# schematic_ult.net
KiCad netlist of a schematic drawn in EAGLE
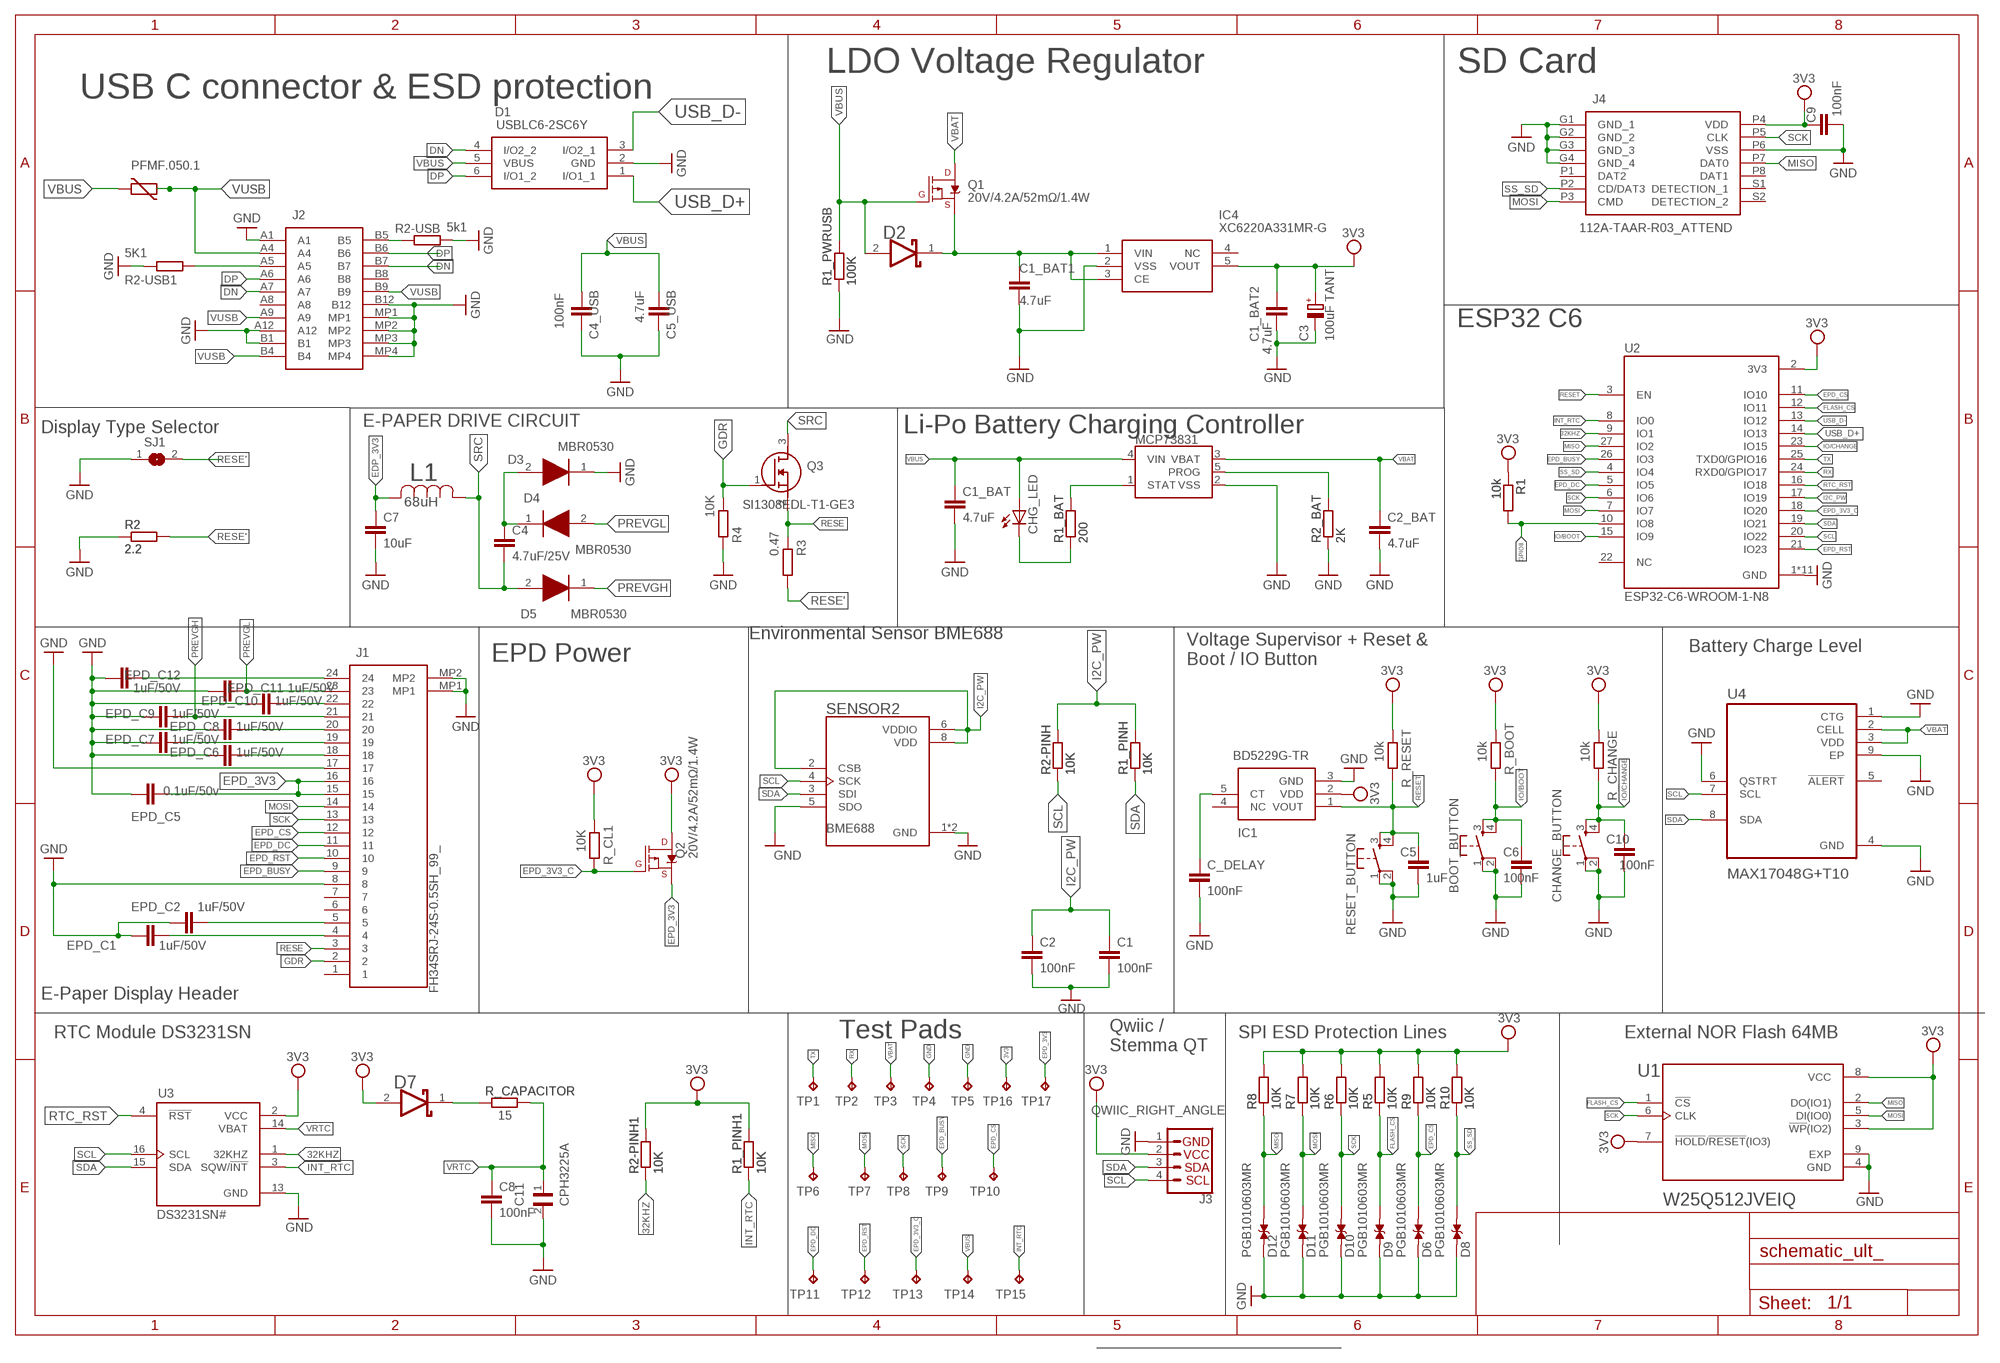
[diagram p0: schematic, sheet 1]

(export (version "E")
  (design (tool "Eeschema 10.0.6"))
  (components
    (comp (ref "BOOT_BUTTON")
      (value "BUTTON_CUSYOMV1")
      (footprint "eagle-import:MYBUTTON")
      (libsource (lib "eagle-import") (part "BUTTON_CUSYOMV1"))
    )
    (comp (ref "C1")
      (value "100nF")
      (footprint "eagle-import:EAGLE-LTSPICE_C0402")
      (libsource (lib "eagle-import") (part "EAGLE-LTSPICE_CC0402"))
    )
    (comp (ref "C1_BAT")
      (value "4.7uF")
      (footprint "eagle-import:EAGLE-LTSPICE_C0402")
      (libsource (lib "eagle-import") (part "EAGLE-LTSPICE_CC0402"))
    )
    (comp (ref "C1_BAT1")
      (value "4.7uF")
      (footprint "eagle-import:ESP32_WROVER_EAGLE-LTSPICE_C0402")
      (libsource (lib "eagle-import") (part "ESP32_WROVER_EAGLE-LTSPICE_CC0402"))
    )
    (comp (ref "C1_BAT2")
      (value "4.7uF")
      (footprint "eagle-import:ESP32_WROVER_EAGLE-LTSPICE_C0402")
      (libsource (lib "eagle-import") (part "ESP32_WROVER_EAGLE-LTSPICE_CC0402"))
    )
    (comp (ref "C2")
      (value "100nF")
      (footprint "eagle-import:EAGLE-LTSPICE_C0402")
      (libsource (lib "eagle-import") (part "EAGLE-LTSPICE_CC0402"))
    )
    (comp (ref "C2_BAT")
      (value "4.7uF")
      (footprint "eagle-import:EAGLE-LTSPICE_C0402")
      (libsource (lib "eagle-import") (part "EAGLE-LTSPICE_CC0402"))
    )
    (comp (ref "C3")
      (value "100uF TANT")
      (footprint "eagle-import:RCL_CT3528")
      (libsource (lib "eagle-import") (part "RCL_CPOL-EUCT3528"))
    )
    (comp (ref "C4")
      (value "4.7uF/25V")
      (footprint "eagle-import:EAGLE-LTSPICE_C0402")
      (libsource (lib "eagle-import") (part "EAGLE-LTSPICE_CC0402"))
    )
    (comp (ref "C4_USB")
      (value "100nF")
      (footprint "eagle-import:EAGLE-LTSPICE_C0402")
      (libsource (lib "eagle-import") (part "EAGLE-LTSPICE_CC0402"))
    )
    (comp (ref "C5")
      (value "1uF")
      (footprint "eagle-import:EAGLE-LTSPICE_C0402")
      (libsource (lib "eagle-import") (part "EAGLE-LTSPICE_CC0402"))
    )
    (comp (ref "C5_USB")
      (value "4.7uF")
      (footprint "eagle-import:EAGLE-LTSPICE_C0402")
      (libsource (lib "eagle-import") (part "EAGLE-LTSPICE_CC0402"))
    )
    (comp (ref "C6")
      (value "100nF")
      (footprint "eagle-import:EAGLE-LTSPICE_C0402")
      (libsource (lib "eagle-import") (part "EAGLE-LTSPICE_CC0402"))
    )
    (comp (ref "C7")
      (value "10uF")
      (footprint "eagle-import:EAGLE-LTSPICE_C0402")
      (libsource (lib "eagle-import") (part "EAGLE-LTSPICE_CC0402"))
    )
    (comp (ref "C8")
      (value "100nF")
      (footprint "eagle-import:EAGLE-LTSPICE_C0402")
      (libsource (lib "eagle-import") (part "EAGLE-LTSPICE_CC0402"))
    )
    (comp (ref "C9")
      (value "100nF")
      (footprint "eagle-import:EAGLE-LTSPICE_C0402")
      (libsource (lib "eagle-import") (part "EAGLE-LTSPICE_CC0402"))
    )
    (comp (ref "C10")
      (value "100nF")
      (footprint "eagle-import:EAGLE-LTSPICE_C0402")
      (libsource (lib "eagle-import") (part "EAGLE-LTSPICE_CC0402"))
    )
    (comp (ref "C11")
      (value "CPH3225A")
      (footprint "eagle-import:CAPCP3225X100N")
      (fields (field (name "MF") "Seiko Instruments"))
      (libsource (lib "eagle-import") (part "CPH3225A"))
    )
    (comp (ref "CHANGE_BUTTON")
      (value "BUTTON_CUSYOMV1")
      (footprint "eagle-import:MYBUTTON")
      (libsource (lib "eagle-import") (part "BUTTON_CUSYOMV1"))
    )
    (comp (ref "CHG_LED")
      (value "ADAFRUIT_LEDCHIP-LED0603")
      (footprint "eagle-import:ADAFRUIT_CHIP-LED0603")
      (libsource (lib "eagle-import") (part "ADAFRUIT_LEDCHIP-LED0603"))
    )
    (comp (ref "C_DELAY")
      (value "100nF")
      (footprint "eagle-import:EAGLE-LTSPICE_C0402")
      (libsource (lib "eagle-import") (part "EAGLE-LTSPICE_CC0402"))
    )
    (comp (ref "D1")
      (value "USBLC6-2SC6Y")
      (footprint "eagle-import:SOT95P280X145-6N")
      (fields (field (name "MF") "STMicroelectronics"))
      (libsource (lib "eagle-import") (part "USBLC6-2SC6Y"))
    )
    (comp (ref "D2")
      (value "ESP32_WROVER_AVX---SD0805S020S1R0_AVX_SD0805S020S1R0_0_0AVX_SD0805S020S1R0_0_0")
      (footprint "eagle-import:ESP32_WROVER_AVX---SD0805S020S1R0_AVX_SD0805S020S1R0_0")
      (fields
        (field (name "DIGIKEY_PART_NUMBER") "478-7800-1-ND")
        (field (name "MF") "AVX")
        (field (name "MOUSER_PART_NUMBER") "581-SD0805S020S1R0")
      )
      (libsource (lib "eagle-import") (part "ESP32_WROVER_AVX---SD0805S020S1R0_AVX_SD0805S020S1R0_0_0AVX_SD0805S020S1R0_0_0"))
    )
    (comp (ref "D3")
      (value "MBR0530")
      (footprint "eagle-import:SOD3716X135N")
      (fields (field (name "MF") "ON Semiconductor"))
      (libsource (lib "eagle-import") (part "MBR0530"))
    )
    (comp (ref "D4")
      (value "MBR0530")
      (footprint "eagle-import:SOD3716X135N")
      (fields (field (name "MF") "ON Semiconductor"))
      (libsource (lib "eagle-import") (part "MBR0530"))
    )
    (comp (ref "D5")
      (value "MBR0530")
      (footprint "eagle-import:SOD3716X135N")
      (fields (field (name "MF") "ON Semiconductor"))
      (libsource (lib "eagle-import") (part "MBR0530"))
    )
    (comp (ref "D6")
      (value "PGB1010603MR")
      (footprint "eagle-import:DIOC1608X36N")
      (fields (field (name "MF") "Littelfuse Inc."))
      (libsource (lib "eagle-import") (part "PGB1010603MR"))
    )
    (comp (ref "D7")
      (value "ESP32_WROVER_AVX---SD0805S020S1R0_AVX_SD0805S020S1R0_0_0AVX_SD0805S020S1R0_0_0")
      (footprint "eagle-import:ESP32_WROVER_AVX---SD0805S020S1R0_AVX_SD0805S020S1R0_0")
      (fields
        (field (name "DIGIKEY_PART_NUMBER") "478-7800-1-ND")
        (field (name "MF") "AVX")
        (field (name "MOUSER_PART_NUMBER") "581-SD0805S020S1R0")
      )
      (libsource (lib "eagle-import") (part "ESP32_WROVER_AVX---SD0805S020S1R0_AVX_SD0805S020S1R0_0_0AVX_SD0805S020S1R0_0_0"))
    )
    (comp (ref "D8")
      (value "PGB1010603MR")
      (footprint "eagle-import:DIOC1608X36N")
      (fields (field (name "MF") "Littelfuse Inc."))
      (libsource (lib "eagle-import") (part "PGB1010603MR"))
    )
    (comp (ref "D9")
      (value "PGB1010603MR")
      (footprint "eagle-import:DIOC1608X36N")
      (fields (field (name "MF") "Littelfuse Inc."))
      (libsource (lib "eagle-import") (part "PGB1010603MR"))
    )
    (comp (ref "D10")
      (value "PGB1010603MR")
      (footprint "eagle-import:DIOC1608X36N")
      (fields (field (name "MF") "Littelfuse Inc."))
      (libsource (lib "eagle-import") (part "PGB1010603MR"))
    )
    (comp (ref "D11")
      (value "PGB1010603MR")
      (footprint "eagle-import:DIOC1608X36N")
      (fields (field (name "MF") "Littelfuse Inc."))
      (libsource (lib "eagle-import") (part "PGB1010603MR"))
    )
    (comp (ref "D12")
      (value "PGB1010603MR")
      (footprint "eagle-import:DIOC1608X36N")
      (fields (field (name "MF") "Littelfuse Inc."))
      (libsource (lib "eagle-import") (part "PGB1010603MR"))
    )
    (comp (ref "EPD_C1")
      (value "1uF/50V")
      (footprint "eagle-import:EAGLE-LTSPICE_C0402")
      (libsource (lib "eagle-import") (part "EAGLE-LTSPICE_CC0402"))
    )
    (comp (ref "EPD_C2")
      (value "1uF/50V")
      (footprint "eagle-import:EAGLE-LTSPICE_C0402")
      (libsource (lib "eagle-import") (part "EAGLE-LTSPICE_CC0402"))
    )
    (comp (ref "EPD_C5")
      (value "0.1uF/50v")
      (footprint "eagle-import:EAGLE-LTSPICE_C0402")
      (libsource (lib "eagle-import") (part "EAGLE-LTSPICE_CC0402"))
    )
    (comp (ref "EPD_C6")
      (value "1uF/50V")
      (footprint "eagle-import:EAGLE-LTSPICE_C0402")
      (libsource (lib "eagle-import") (part "EAGLE-LTSPICE_CC0402"))
    )
    (comp (ref "EPD_C7")
      (value "1uF/50V")
      (footprint "eagle-import:EAGLE-LTSPICE_C0402")
      (libsource (lib "eagle-import") (part "EAGLE-LTSPICE_CC0402"))
    )
    (comp (ref "EPD_C8")
      (value "1uF/50V")
      (footprint "eagle-import:EAGLE-LTSPICE_C0402")
      (libsource (lib "eagle-import") (part "EAGLE-LTSPICE_CC0402"))
    )
    (comp (ref "EPD_C9")
      (value "1uF/50V")
      (footprint "eagle-import:EAGLE-LTSPICE_C0402")
      (libsource (lib "eagle-import") (part "EAGLE-LTSPICE_CC0402"))
    )
    (comp (ref "EPD_C10")
      (value "1uF/50V")
      (footprint "eagle-import:EAGLE-LTSPICE_C0402")
      (libsource (lib "eagle-import") (part "EAGLE-LTSPICE_CC0402"))
    )
    (comp (ref "EPD_C11")
      (value "1uF/50V")
      (footprint "eagle-import:EAGLE-LTSPICE_C0402")
      (libsource (lib "eagle-import") (part "EAGLE-LTSPICE_CC0402"))
    )
    (comp (ref "EPD_C12")
      (value "1uF/50V")
      (footprint "eagle-import:EAGLE-LTSPICE_C0402")
      (libsource (lib "eagle-import") (part "EAGLE-LTSPICE_CC0402"))
    )
    (comp (ref "IC1")
      (value "BD5229G-TR")
      (footprint "eagle-import:SOT95P280X125-5N")
      (fields (field (name "MOUSER_PART_NUMBER") "755-BD5229G-TR"))
      (libsource (lib "eagle-import") (part "BD5229G-TR"))
    )
    (comp (ref "IC4")
      (value "XC6220A331MR-G")
      (footprint "eagle-import:SOT95P280X120-5N")
      (fields (field (name "MOUSER_PART_NUMBER") "865-XC6220A331MR-G"))
      (libsource (lib "eagle-import") (part "XC6220A331MR-G"))
    )
    (comp (ref "J1")
      (value "FH34SRJ-24S-0.5SH_99_")
      (footprint "eagle-import:FH34SRJ24S05SH99")
      (fields
        (field (name "MANUFACTURER_PART_NUMBER") "FH34SRJ-24S-0.5SH(99)")
        (field (name "MOUSER_PART_NUMBER") "798-FH34SRJ24S05SH99")
      )
      (libsource (lib "eagle-import") (part "FH34SRJ-24S-0.5SH_99_"))
    )
    (comp (ref "J2")
      (value "SAMACSYS_PARTS_USB4110-GF-A")
      (footprint "eagle-import:SAMACSYS_PARTS_USB4110GFA")
      (fields
        (field (name "MANUFACTURER_PART_NUMBER") "USB4110-GF-A")
        (field (name "MOUSER_PART_NUMBER") "640-USB4110-GF-A")
      )
      (libsource (lib "eagle-import") (part "SAMACSYS_PARTS_USB4110-GF-A"))
    )
    (comp (ref "J3")
      (value "QWIIC_RIGHT_ANGLE")
      (footprint "eagle-import:JST04_1MM_RA")
      (libsource (lib "eagle-import") (part "QWIIC_CONNECTORJS-1MM"))
    )
    (comp (ref "J4")
      (value "112A-TAAR-R03_ATTEND")
      (footprint "eagle-import:112ATAARR03ATTEND")
      (fields (field (name "MANUFACTURER_PART_NUMBER") "112A-TAAR-R03 ATTEND"))
      (libsource (lib "eagle-import") (part "112A-TAAR-R03_ATTEND"))
    )
    (comp (ref "L1")
      (value "68uH")
      (footprint "eagle-import:IND_4828-WE-TPC_WRE")
      (fields
        (field (name "MANUFACTURER_PART_NUMBER") "744043680")
        (field (name "COPYRIGHT") "Copyright (C) 2024 Ultra Librarian. All rights reserved.")
      )
      (libsource (lib "eagle-import") (part "744043680IND_4828-WE-TPC_WRE"))
    )
    (comp (ref "MCP73831")
      (value "ESP32_WROVER_SPARKFUN-IC-POWER_MCP73831")
      (footprint "eagle-import:ESP32_WROVER_SPARKFUN-IC-POWER_SOT23-5")
      (libsource (lib "eagle-import") (part "ESP32_WROVER_SPARKFUN-IC-POWER_MCP73831"))
    )
    (comp (ref "PFMF.050.1")
      (value "ESP32C6_VARISTORCN1812")
      (footprint "eagle-import:ESP32C6_VARISTOR_CT_CN1812")
      (libsource (lib "eagle-import") (part "ESP32C6_VARISTORCN1812"))
    )
    (comp (ref "Q1")
      (value "20V/4.2A/52mΩ/1.4W")
      (footprint "eagle-import:ESP32_WROVER_SPARKFUN-DISCRETESEMI_SOT23-3")
      (libsource (lib "eagle-import") (part "ESP32_WROVER_SPARKFUN-DISCRETESEMI_MOSFET_PCH-DMG2305UX-7"))
    )
    (comp (ref "Q2")
      (value "20V/4.2A/52mΩ/1.4W")
      (footprint "eagle-import:ESP32_WROVER_SPARKFUN-DISCRETESEMI_SOT23-3")
      (libsource (lib "eagle-import") (part "ESP32_WROVER_SPARKFUN-DISCRETESEMI_MOSFET_PCH-DMG2305UX-7"))
    )
    (comp (ref "Q3")
      (value "SI1308EDL-T1-GE3")
      (footprint "eagle-import:SOT65P210X110-3N")
      (fields (field (name "MF") "Vishay Siliconix"))
      (libsource (lib "eagle-import") (part "SI1308EDL-T1-GE3"))
    )
    (comp (ref "R1")
      (value "10k")
      (footprint "eagle-import:ESP32_WROVER_EAGLE-LTSPICE_R0402")
      (libsource (lib "eagle-import") (part "ESP32_WROVER_EAGLE-LTSPICE_RR0402"))
    )
    (comp (ref "R1_BAT")
      (value "200")
      (footprint "eagle-import:ESP32_WROVER_EAGLE-LTSPICE_R0402")
      (libsource (lib "eagle-import") (part "ESP32_WROVER_EAGLE-LTSPICE_RR0402"))
    )
    (comp (ref "R1_PINH")
      (value "10K")
      (footprint "eagle-import:ESP32_WROVER_EAGLE-LTSPICE_R0402")
      (libsource (lib "eagle-import") (part "ESP32_WROVER_EAGLE-LTSPICE_RR0402"))
    )
    (comp (ref "R1_PINH1")
      (value "10K")
      (footprint "eagle-import:ESP32_WROVER_EAGLE-LTSPICE_R0402")
      (libsource (lib "eagle-import") (part "ESP32_WROVER_EAGLE-LTSPICE_RR0402"))
    )
    (comp (ref "R1_PWRUSB")
      (value "100K")
      (footprint "eagle-import:ESP32_WROVER_EAGLE-LTSPICE_R0402")
      (libsource (lib "eagle-import") (part "ESP32_WROVER_EAGLE-LTSPICE_RR0402"))
    )
    (comp (ref "R2")
      (value "2.2")
      (footprint "eagle-import:ESP32_WROVER_EAGLE-LTSPICE_R0402")
      (libsource (lib "eagle-import") (part "ESP32_WROVER_EAGLE-LTSPICE_RR0402"))
    )
    (comp (ref "R2-PINH")
      (value "10K")
      (footprint "eagle-import:ESP32_WROVER_EAGLE-LTSPICE_R0402")
      (libsource (lib "eagle-import") (part "ESP32_WROVER_EAGLE-LTSPICE_RR0402"))
    )
    (comp (ref "R2-PINH1")
      (value "10K")
      (footprint "eagle-import:ESP32_WROVER_EAGLE-LTSPICE_R0402")
      (libsource (lib "eagle-import") (part "ESP32_WROVER_EAGLE-LTSPICE_RR0402"))
    )
    (comp (ref "R2-USB")
      (value "5k1")
      (footprint "eagle-import:ESP32_WROVER_EAGLE-LTSPICE_R0402")
      (libsource (lib "eagle-import") (part "ESP32_WROVER_EAGLE-LTSPICE_RR0402"))
    )
    (comp (ref "R2-USB1")
      (value "5K1")
      (footprint "eagle-import:ESP32_WROVER_EAGLE-LTSPICE_R0402")
      (fields (field (name "SPICEPREFIX") "R2-USB1"))
      (libsource (lib "eagle-import") (part "ESP32_WROVER_EAGLE-LTSPICE_RR0402"))
    )
    (comp (ref "R2_BAT")
      (value "2K")
      (footprint "eagle-import:ESP32_WROVER_EAGLE-LTSPICE_R0402")
      (libsource (lib "eagle-import") (part "ESP32_WROVER_EAGLE-LTSPICE_RR0402"))
    )
    (comp (ref "R3")
      (value "0.47")
      (footprint "eagle-import:ESP32_WROVER_EAGLE-LTSPICE_R0402")
      (libsource (lib "eagle-import") (part "ESP32_WROVER_EAGLE-LTSPICE_RR0402"))
    )
    (comp (ref "R4")
      (value "10K")
      (footprint "eagle-import:ESP32_WROVER_EAGLE-LTSPICE_R0402")
      (libsource (lib "eagle-import") (part "ESP32_WROVER_EAGLE-LTSPICE_RR0402"))
    )
    (comp (ref "R5")
      (value "10K")
      (footprint "eagle-import:ESP32_WROVER_EAGLE-LTSPICE_R0402")
      (libsource (lib "eagle-import") (part "ESP32_WROVER_EAGLE-LTSPICE_RR0402"))
    )
    (comp (ref "R6")
      (value "10K")
      (footprint "eagle-import:ESP32_WROVER_EAGLE-LTSPICE_R0402")
      (libsource (lib "eagle-import") (part "ESP32_WROVER_EAGLE-LTSPICE_RR0402"))
    )
    (comp (ref "R7")
      (value "10K")
      (footprint "eagle-import:ESP32_WROVER_EAGLE-LTSPICE_R0402")
      (libsource (lib "eagle-import") (part "ESP32_WROVER_EAGLE-LTSPICE_RR0402"))
    )
    (comp (ref "R8")
      (value "10K")
      (footprint "eagle-import:ESP32_WROVER_EAGLE-LTSPICE_R0402")
      (libsource (lib "eagle-import") (part "ESP32_WROVER_EAGLE-LTSPICE_RR0402"))
    )
    (comp (ref "R9")
      (value "10K")
      (footprint "eagle-import:ESP32_WROVER_EAGLE-LTSPICE_R0402")
      (libsource (lib "eagle-import") (part "ESP32_WROVER_EAGLE-LTSPICE_RR0402"))
    )
    (comp (ref "R10")
      (value "10K")
      (footprint "eagle-import:ESP32_WROVER_EAGLE-LTSPICE_R0402")
      (libsource (lib "eagle-import") (part "ESP32_WROVER_EAGLE-LTSPICE_RR0402"))
    )
    (comp (ref "RESET_BUTTON")
      (value "BUTTON_CUSYOMV1")
      (footprint "eagle-import:MYBUTTON")
      (libsource (lib "eagle-import") (part "BUTTON_CUSYOMV1"))
    )
    (comp (ref "R_BOOT")
      (value "10k")
      (footprint "eagle-import:ESP32_WROVER_EAGLE-LTSPICE_R0402")
      (libsource (lib "eagle-import") (part "ESP32_WROVER_EAGLE-LTSPICE_RR0402"))
    )
    (comp (ref "R_CAPACITOR")
      (value "15")
      (footprint "eagle-import:ESP32_WROVER_EAGLE-LTSPICE_R0402")
      (libsource (lib "eagle-import") (part "ESP32_WROVER_EAGLE-LTSPICE_RR0402"))
    )
    (comp (ref "R_CHANGE")
      (value "10k")
      (footprint "eagle-import:ESP32_WROVER_EAGLE-LTSPICE_R0402")
      (libsource (lib "eagle-import") (part "ESP32_WROVER_EAGLE-LTSPICE_RR0402"))
    )
    (comp (ref "R_CL1")
      (value "10K")
      (footprint "eagle-import:ESP32_WROVER_EAGLE-LTSPICE_R0402")
      (libsource (lib "eagle-import") (part "ESP32_WROVER_EAGLE-LTSPICE_RR0402"))
    )
    (comp (ref "R_RESET")
      (value "10k")
      (footprint "eagle-import:ESP32_WROVER_EAGLE-LTSPICE_R0402")
      (libsource (lib "eagle-import") (part "ESP32_WROVER_EAGLE-LTSPICE_RR0402"))
    )
    (comp (ref "SENSOR2")
      (value "ESP32_WROVER_BME680_BME680")
      (footprint "eagle-import:ESP32_WROVER_BME680_PSON80P300X300X100-8N")
      (fields (field (name "MF") "Bosch Sensortec") (field (name "MP") "BME680"))
      (libsource (lib "eagle-import") (part "ESP32_WROVER_BME680_BME680"))
    )
    (comp (ref "SJ1") (value "SJ") (footprint "eagle-import:SJ") (libsource (lib "eagle-import") (part "SJ")))
    (comp (ref "TP1")
      (value "TPTP20R")
      (footprint "eagle-import:TP20R")
      (libsource (lib "eagle-import") (part "TPTP20R"))
    )
    (comp (ref "TP2")
      (value "TPTP20R")
      (footprint "eagle-import:TP20R")
      (libsource (lib "eagle-import") (part "TPTP20R"))
    )
    (comp (ref "TP3")
      (value "TPTP20R")
      (footprint "eagle-import:TP20R")
      (libsource (lib "eagle-import") (part "TPTP20R"))
    )
    (comp (ref "TP4")
      (value "TPTP20R")
      (footprint "eagle-import:TP20R")
      (libsource (lib "eagle-import") (part "TPTP20R"))
    )
    (comp (ref "TP5")
      (value "TPTP20R")
      (footprint "eagle-import:TP20R")
      (libsource (lib "eagle-import") (part "TPTP20R"))
    )
    (comp (ref "TP6")
      (value "TPTP20R")
      (footprint "eagle-import:TP20R")
      (libsource (lib "eagle-import") (part "TPTP20R"))
    )
    (comp (ref "TP7")
      (value "TPTP20R")
      (footprint "eagle-import:TP20R")
      (libsource (lib "eagle-import") (part "TPTP20R"))
    )
    (comp (ref "TP8")
      (value "TPTP20R")
      (footprint "eagle-import:TP20R")
      (libsource (lib "eagle-import") (part "TPTP20R"))
    )
    (comp (ref "TP9")
      (value "TPTP20R")
      (footprint "eagle-import:TP20R")
      (libsource (lib "eagle-import") (part "TPTP20R"))
    )
    (comp (ref "TP10")
      (value "TPTP20R")
      (footprint "eagle-import:TP20R")
      (libsource (lib "eagle-import") (part "TPTP20R"))
    )
    (comp (ref "TP11")
      (value "TPTP20R")
      (footprint "eagle-import:TP20R")
      (libsource (lib "eagle-import") (part "TPTP20R"))
    )
    (comp (ref "TP12")
      (value "TPTP20R")
      (footprint "eagle-import:TP20R")
      (libsource (lib "eagle-import") (part "TPTP20R"))
    )
    (comp (ref "TP13")
      (value "TPTP20R")
      (footprint "eagle-import:TP20R")
      (libsource (lib "eagle-import") (part "TPTP20R"))
    )
    (comp (ref "TP14")
      (value "TPTP20R")
      (footprint "eagle-import:TP20R")
      (libsource (lib "eagle-import") (part "TPTP20R"))
    )
    (comp (ref "TP15")
      (value "TPTP20R")
      (footprint "eagle-import:TP20R")
      (libsource (lib "eagle-import") (part "TPTP20R"))
    )
    (comp (ref "TP16")
      (value "TPTP20R")
      (footprint "eagle-import:TP20R")
      (libsource (lib "eagle-import") (part "TPTP20R"))
    )
    (comp (ref "TP17")
      (value "TPTP20R")
      (footprint "eagle-import:TP20R")
      (libsource (lib "eagle-import") (part "TPTP20R"))
    )
    (comp (ref "U1")
      (value "W25Q512JVEIQ")
      (footprint "eagle-import:SON127P600X800X80-9N")
      (fields (field (name "MF") "Winbond Electronics"))
      (libsource (lib "eagle-import") (part "W25Q512JVEIQ"))
    )
    (comp (ref "U2")
      (value "ESP32-C6-WROOM-1-N8")
      (footprint "eagle-import:XCVR_ESP32-C6-WROOM-1-N8")
      (fields (field (name "MF") "Espressif Systems"))
      (libsource (lib "eagle-import") (part "ESP32-C6-WROOM-1-N8"))
    )
    (comp (ref "U3")
      (value "DS3231SN#")
      (footprint "eagle-import:SOIC127P1032X265-16N")
      (fields (field (name "MF") "Analog Devices"))
      (libsource (lib "eagle-import") (part "DS3231SN#"))
    )
    (comp (ref "U4")
      (value "MAX17048G+T10")
      (footprint "eagle-import:SON50P200X200X80-9N")
      (fields (field (name "MF") "Analog Devices"))
      (libsource (lib "eagle-import") (part "MAX17048G+T10"))
    )
  )
  (nets
    (net (code "1") (name "3V3") (class "Default")
      (node (ref "C1_BAT2") (pin "1") (pinfunction "1_1") (pintype "passive"))
      (node (ref "C3") (pin "+") (pinfunction "+_+") (pintype "passive"))
      (node (ref "C9") (pin "2") (pinfunction "2_2") (pintype "passive"))
      (node (ref "D7") (pin "2") (pinfunction "ANODE_2") (pintype "bidirectional"))
      (node (ref "IC1") (pin "2") (pinfunction "VDD_2") (pintype "bidirectional"))
      (node (ref "IC4") (pin "5") (pinfunction "VOUT_5") (pintype "bidirectional"))
      (node (ref "J3") (pin "2") (pinfunction "2_2") (pintype "power_in"))
      (node (ref "J4") (pin "P4") (pinfunction "VDD_P4") (pintype "bidirectional"))
      (node (ref "Q2") (pin "3") (pinfunction "D_3") (pintype "bidirectional"))
      (node (ref "R1") (pin "1") (pinfunction "1_1") (pintype "passive"))
      (node (ref "R10") (pin "2") (pinfunction "2_2") (pintype "passive"))
      (node (ref "R1_PINH1") (pin "2") (pinfunction "2_2") (pintype "passive"))
      (node (ref "R2-PINH1") (pin "2") (pinfunction "2_2") (pintype "passive"))
      (node (ref "R5") (pin "2") (pinfunction "2_2") (pintype "passive"))
      (node (ref "R6") (pin "2") (pinfunction "2_2") (pintype "passive"))
      (node (ref "R7") (pin "2") (pinfunction "2_2") (pintype "passive"))
      (node (ref "R8") (pin "2") (pinfunction "2_2") (pintype "passive"))
      (node (ref "R9") (pin "2") (pinfunction "2_2") (pintype "passive"))
      (node (ref "R_BOOT") (pin "2") (pinfunction "2_2") (pintype "passive"))
      (node (ref "R_CHANGE") (pin "2") (pinfunction "2_2") (pintype "passive"))
      (node (ref "R_CL1") (pin "2") (pinfunction "2_2") (pintype "passive"))
      (node (ref "R_RESET") (pin "2") (pinfunction "2_2") (pintype "passive"))
      (node (ref "TP16") (pin "TP") (pinfunction "TP_TP") (pintype "input"))
      (node (ref "U1") (pin "3") (pinfunction "~{WP}(IO2)_3") (pintype "bidirectional"))
      (node (ref "U1") (pin "7") (pinfunction "~{HOLD}/~{RESET}(IO3)_7") (pintype "bidirectional"))
      (node (ref "U1") (pin "8") (pinfunction "VCC_8") (pintype "power_in"))
      (node (ref "U2") (pin "2") (pinfunction "3V3_2") (pintype "power_in"))
      (node (ref "U3") (pin "2") (pinfunction "VCC_2") (pintype "power_in"))
    )
    (net (code "2") (name "32KHZ") (class "Default")
      (node (ref "R2-PINH1") (pin "1") (pinfunction "1_1") (pintype "passive"))
      (node (ref "U2") (pin "9") (pinfunction "IO1_9") (pintype "bidirectional"))
      (node (ref "U3") (pin "1") (pinfunction "32KHZ_1") (pintype "output"))
    )
    (net (code "3") (name "DN") (class "Default")
      (node (ref "D1") (pin "4") (pinfunction "I/O2_2_4") (pintype "bidirectional"))
      (node (ref "J2") (pin "A7") (pinfunction "A7_A7") (pintype "bidirectional"))
      (node (ref "J2") (pin "B7") (pinfunction "B7_B7") (pintype "bidirectional"))
    )
    (net (code "4") (name "DP") (class "Default")
      (node (ref "D1") (pin "6") (pinfunction "I/O1_2_6") (pintype "bidirectional"))
      (node (ref "J2") (pin "A6") (pinfunction "A6_A6") (pintype "bidirectional"))
      (node (ref "J2") (pin "B6") (pinfunction "B6_B6") (pintype "bidirectional"))
    )
    (net (code "5") (name "EDP_3V3") (class "Default")
      (node (ref "C7") (pin "1") (pinfunction "1_1") (pintype "passive"))
      (node (ref "L1") (pin "2") (pinfunction "2_2") (pintype "passive"))
    )
    (net (code "6") (name "EPD_3V3") (class "Default")
      (node (ref "EPD_C5") (pin "2") (pinfunction "2_2") (pintype "passive"))
      (node (ref "J1") (pin "15") (pinfunction "15_15") (pintype "bidirectional"))
      (node (ref "J1") (pin "16") (pinfunction "16_16") (pintype "bidirectional"))
      (node (ref "Q2") (pin "2") (pinfunction "S_2") (pintype "bidirectional"))
      (node (ref "TP17") (pin "TP") (pinfunction "TP_TP") (pintype "input"))
    )
    (net (code "7") (name "EPD_3V3_C") (class "Default")
      (node (ref "Q2") (pin "1") (pinfunction "G_1") (pintype "bidirectional"))
      (node (ref "R_CL1") (pin "1") (pinfunction "1_1") (pintype "passive"))
      (node (ref "TP13") (pin "TP") (pinfunction "TP_TP") (pintype "input"))
      (node (ref "U2") (pin "18") (pinfunction "IO20_18") (pintype "bidirectional"))
    )
    (net (code "8") (name "EPD_BUSY") (class "Default")
      (node (ref "J1") (pin "9") (pinfunction "9_9") (pintype "bidirectional"))
      (node (ref "TP9") (pin "TP") (pinfunction "TP_TP") (pintype "input"))
      (node (ref "U2") (pin "26") (pinfunction "IO3_26") (pintype "bidirectional"))
    )
    (net (code "9") (name "EPD_CS") (class "Default")
      (node (ref "D6") (pin "2") (pinfunction "2_2") (pintype "passive"))
      (node (ref "J1") (pin "12") (pinfunction "12_12") (pintype "bidirectional"))
      (node (ref "R9") (pin "1") (pinfunction "1_1") (pintype "passive"))
      (node (ref "TP10") (pin "TP") (pinfunction "TP_TP") (pintype "input"))
      (node (ref "U2") (pin "11") (pinfunction "IO10_11") (pintype "bidirectional"))
    )
    (net (code "10") (name "EPD_DC") (class "Default")
      (node (ref "J1") (pin "11") (pinfunction "11_11") (pintype "bidirectional"))
      (node (ref "TP11") (pin "TP") (pinfunction "TP_TP") (pintype "input"))
      (node (ref "U2") (pin "5") (pinfunction "IO5_5") (pintype "bidirectional"))
    )
    (net (code "11") (name "EPD_RST") (class "Default")
      (node (ref "J1") (pin "10") (pinfunction "10_10") (pintype "bidirectional"))
      (node (ref "TP12") (pin "TP") (pinfunction "TP_TP") (pintype "input"))
      (node (ref "U2") (pin "21") (pinfunction "IO23_21") (pintype "bidirectional"))
    )
    (net (code "12") (name "FLASH_CS") (class "Default")
      (node (ref "D9") (pin "2") (pinfunction "2_2") (pintype "passive"))
      (node (ref "R5") (pin "1") (pinfunction "1_1") (pintype "passive"))
      (node (ref "U1") (pin "1") (pinfunction "~{CS}_1") (pintype "input"))
      (node (ref "U2") (pin "12") (pinfunction "IO11_12") (pintype "bidirectional"))
    )
    (net (code "13") (name "GDR") (class "Default")
      (node (ref "J1") (pin "2") (pinfunction "2_2") (pintype "bidirectional"))
      (node (ref "Q3") (pin "1") (pinfunction "G_1") (pintype "bidirectional"))
      (node (ref "R4") (pin "2") (pinfunction "2_2") (pintype "passive"))
    )
    (net (code "14") (name "GND") (class "Default")
      (node (ref "BOOT_BUTTON") (pin "1") (pinfunction "1_1") (pintype "passive"))
      (node (ref "BOOT_BUTTON") (pin "2") (pinfunction "2_2") (pintype "passive"))
      (node (ref "C1") (pin "2") (pinfunction "2_2") (pintype "passive"))
      (node (ref "C10") (pin "2") (pinfunction "2_2") (pintype "passive"))
      (node (ref "C11") (pin "2") (pinfunction "2_2") (pintype "passive"))
      (node (ref "C1_BAT") (pin "2") (pinfunction "2_2") (pintype "passive"))
      (node (ref "C1_BAT1") (pin "2") (pinfunction "2_2") (pintype "passive"))
      (node (ref "C1_BAT2") (pin "2") (pinfunction "2_2") (pintype "passive"))
      (node (ref "C2") (pin "2") (pinfunction "2_2") (pintype "passive"))
      (node (ref "C2_BAT") (pin "2") (pinfunction "2_2") (pintype "passive"))
      (node (ref "C3") (pin "-") (pinfunction "-_-") (pintype "passive"))
      (node (ref "C4_USB") (pin "2") (pinfunction "2_2") (pintype "passive"))
      (node (ref "C5") (pin "2") (pinfunction "2_2") (pintype "passive"))
      (node (ref "C5_USB") (pin "2") (pinfunction "2_2") (pintype "passive"))
      (node (ref "C6") (pin "2") (pinfunction "2_2") (pintype "passive"))
      (node (ref "C7") (pin "2") (pinfunction "2_2") (pintype "passive"))
      (node (ref "C8") (pin "2") (pinfunction "2_2") (pintype "passive"))
      (node (ref "C9") (pin "1") (pinfunction "1_1") (pintype "passive"))
      (node (ref "CHANGE_BUTTON") (pin "1") (pinfunction "1_1") (pintype "passive"))
      (node (ref "CHANGE_BUTTON") (pin "2") (pinfunction "2_2") (pintype "passive"))
      (node (ref "C_DELAY") (pin "2") (pinfunction "2_2") (pintype "passive"))
      (node (ref "D1") (pin "2") (pinfunction "GND_2") (pintype "bidirectional"))
      (node (ref "D10") (pin "1") (pinfunction "1_1") (pintype "passive"))
      (node (ref "D11") (pin "1") (pinfunction "1_1") (pintype "passive"))
      (node (ref "D12") (pin "1") (pinfunction "1_1") (pintype "passive"))
      (node (ref "D3") (pin "1") (pinfunction "K_1") (pintype "bidirectional"))
      (node (ref "D6") (pin "1") (pinfunction "1_1") (pintype "passive"))
      (node (ref "D8") (pin "1") (pinfunction "1_1") (pintype "passive"))
      (node (ref "D9") (pin "1") (pinfunction "1_1") (pintype "passive"))
      (node (ref "EPD_C1") (pin "1") (pinfunction "1_1") (pintype "passive"))
      (node (ref "EPD_C10") (pin "1") (pinfunction "1_1") (pintype "passive"))
      (node (ref "EPD_C11") (pin "1") (pinfunction "1_1") (pintype "passive"))
      (node (ref "EPD_C12") (pin "1") (pinfunction "1_1") (pintype "passive"))
      (node (ref "EPD_C2") (pin "1") (pinfunction "1_1") (pintype "passive"))
      (node (ref "EPD_C5") (pin "1") (pinfunction "1_1") (pintype "passive"))
      (node (ref "EPD_C6") (pin "1") (pinfunction "1_1") (pintype "passive"))
      (node (ref "EPD_C7") (pin "1") (pinfunction "1_1") (pintype "passive"))
      (node (ref "EPD_C8") (pin "1") (pinfunction "1_1") (pintype "passive"))
      (node (ref "EPD_C9") (pin "1") (pinfunction "1_1") (pintype "passive"))
      (node (ref "IC1") (pin "3") (pinfunction "GND_3") (pintype "bidirectional"))
      (node (ref "IC4") (pin "2") (pinfunction "VSS_2") (pintype "bidirectional"))
      (node (ref "J1") (pin "17") (pinfunction "17_17") (pintype "bidirectional"))
      (node (ref "J1") (pin "8") (pinfunction "8_8") (pintype "bidirectional"))
      (node (ref "J1") (pin "MP1") (pinfunction "MP1_MP1") (pintype "bidirectional"))
      (node (ref "J1") (pin "MP2") (pinfunction "MP2_MP2") (pintype "bidirectional"))
      (node (ref "J2") (pin "A1") (pinfunction "A1_A1") (pintype "bidirectional"))
      (node (ref "J2") (pin "A12") (pinfunction "A12_A12") (pintype "bidirectional"))
      (node (ref "J2") (pin "B1") (pinfunction "B1_B1") (pintype "bidirectional"))
      (node (ref "J2") (pin "B12") (pinfunction "B12_B12") (pintype "bidirectional"))
      (node (ref "J2") (pin "MP1") (pinfunction "MP1_MP1") (pintype "bidirectional"))
      (node (ref "J2") (pin "MP2") (pinfunction "MP2_MP2") (pintype "bidirectional"))
      (node (ref "J2") (pin "MP3") (pinfunction "MP3_MP3") (pintype "bidirectional"))
      (node (ref "J2") (pin "MP4") (pinfunction "MP4_MP4") (pintype "bidirectional"))
      (node (ref "J3") (pin "1") (pinfunction "1_1") (pintype "power_in"))
      (node (ref "J4") (pin "G1") (pinfunction "GND_1_G1") (pintype "bidirectional"))
      (node (ref "J4") (pin "G2") (pinfunction "GND_2_G2") (pintype "bidirectional"))
      (node (ref "J4") (pin "G3") (pinfunction "GND_3_G3") (pintype "bidirectional"))
      (node (ref "J4") (pin "G4") (pinfunction "GND_4_G4") (pintype "bidirectional"))
      (node (ref "J4") (pin "P6") (pinfunction "VSS_P6") (pintype "bidirectional"))
      (node (ref "MCP73831") (pin "2") (pinfunction "VSS_2") (pintype "power_in"))
      (node (ref "R1_PWRUSB") (pin "1") (pinfunction "1_1") (pintype "passive"))
      (node (ref "R2") (pin "1") (pinfunction "1_1") (pintype "passive"))
      (node (ref "R2-USB") (pin "2") (pinfunction "2_2") (pintype "passive"))
      (node (ref "R2-USB1") (pin "1") (pinfunction "1_1") (pintype "passive"))
      (node (ref "R2_BAT") (pin "1") (pinfunction "1_1") (pintype "passive"))
      (node (ref "R4") (pin "1") (pinfunction "1_1") (pintype "passive"))
      (node (ref "RESET_BUTTON") (pin "1") (pinfunction "1_1") (pintype "passive"))
      (node (ref "RESET_BUTTON") (pin "2") (pinfunction "2_2") (pintype "passive"))
      (node (ref "SENSOR2") (pin "1") (pinfunction "GND_1") (pintype "power_in"))
      (node (ref "SENSOR2") (pin "5") (pinfunction "SDO_5") (pintype "bidirectional"))
      (node (ref "SENSOR2") (pin "7") (pinfunction "GND_7") (pintype "power_in"))
      (node (ref "SJ1") (pin "1") (pinfunction "1_1") (pintype "passive"))
      (node (ref "TP4") (pin "TP") (pinfunction "TP_TP") (pintype "input"))
      (node (ref "TP5") (pin "TP") (pinfunction "TP_TP") (pintype "input"))
      (node (ref "U1") (pin "4") (pinfunction "GND_4") (pintype "power_in"))
      (node (ref "U1") (pin "9") (pinfunction "EXP_9") (pintype "passive"))
      (node (ref "U2") (pin "1") (pinfunction "GND_1") (pintype "power_in"))
      (node (ref "U2") (pin "28") (pinfunction "GND_28") (pintype "power_in"))
      (node (ref "U2") (pin "29_1") (pinfunction "GND_29_1") (pintype "power_in"))
      (node (ref "U2") (pin "29_2") (pinfunction "GND_29_2") (pintype "power_in"))
      (node (ref "U2") (pin "29_3") (pinfunction "GND_29_3") (pintype "power_in"))
      (node (ref "U2") (pin "29_4") (pinfunction "GND_29_4") (pintype "power_in"))
      (node (ref "U2") (pin "29_5") (pinfunction "GND_29_5") (pintype "power_in"))
      (node (ref "U2") (pin "29_6") (pinfunction "GND_29_6") (pintype "power_in"))
      (node (ref "U2") (pin "29_7") (pinfunction "GND_29_7") (pintype "power_in"))
      (node (ref "U2") (pin "29_8") (pinfunction "GND_29_8") (pintype "power_in"))
      (node (ref "U2") (pin "29_9") (pinfunction "GND_29_9") (pintype "power_in"))
      (node (ref "U3") (pin "13") (pinfunction "GND_13") (pintype "power_in"))
      (node (ref "U4") (pin "1") (pinfunction "CTG_1") (pintype "power_in"))
      (node (ref "U4") (pin "4") (pinfunction "GND_4") (pintype "power_in"))
      (node (ref "U4") (pin "6") (pinfunction "QSTRT_6") (pintype "input"))
      (node (ref "U4") (pin "9") (pinfunction "EP_9") (pintype "power_in"))
    )
    (net (code "15") (name "GPIO8") (class "Default")
      (node (ref "R1") (pin "2") (pinfunction "2_2") (pintype "passive"))
      (node (ref "U2") (pin "10") (pinfunction "IO8_10") (pintype "bidirectional"))
    )
    (net (code "16") (name "I2C_PW") (class "Default")
      (node (ref "C1") (pin "1") (pinfunction "1_1") (pintype "passive"))
      (node (ref "C2") (pin "1") (pinfunction "1_1") (pintype "passive"))
      (node (ref "R1_PINH") (pin "2") (pinfunction "2_2") (pintype "passive"))
      (node (ref "R2-PINH") (pin "2") (pinfunction "2_2") (pintype "passive"))
      (node (ref "SENSOR2") (pin "2") (pinfunction "CSB_2") (pintype "input"))
      (node (ref "SENSOR2") (pin "6") (pinfunction "VDDIO_6") (pintype "power_in"))
      (node (ref "SENSOR2") (pin "8") (pinfunction "VDD_8") (pintype "power_in"))
      (node (ref "U2") (pin "17") (pinfunction "IO19_17") (pintype "bidirectional"))
    )
    (net (code "17") (name "INT_RTC") (class "Default")
      (node (ref "R1_PINH1") (pin "1") (pinfunction "1_1") (pintype "passive"))
      (node (ref "TP15") (pin "TP") (pinfunction "TP_TP") (pintype "input"))
      (node (ref "U2") (pin "8") (pinfunction "IO0_8") (pintype "bidirectional"))
      (node (ref "U3") (pin "3") (pinfunction "SQW/~{INT}_3") (pintype "output"))
    )
    (net (code "18") (name "IO{slash}BOOT") (class "Default")
      (node (ref "BOOT_BUTTON") (pin "3") (pinfunction "3_3") (pintype "passive"))
      (node (ref "BOOT_BUTTON") (pin "4") (pinfunction "4_4") (pintype "passive"))
      (node (ref "C6") (pin "1") (pinfunction "1_1") (pintype "passive"))
      (node (ref "R_BOOT") (pin "1") (pinfunction "1_1") (pintype "passive"))
      (node (ref "U2") (pin "15") (pinfunction "IO9_15") (pintype "bidirectional"))
    )
    (net (code "19") (name "IO{slash}CHANGE") (class "Default")
      (node (ref "C10") (pin "1") (pinfunction "1_1") (pintype "passive"))
      (node (ref "CHANGE_BUTTON") (pin "3") (pinfunction "3_3") (pintype "passive"))
      (node (ref "CHANGE_BUTTON") (pin "4") (pinfunction "4_4") (pintype "passive"))
      (node (ref "R_CHANGE") (pin "1") (pinfunction "1_1") (pintype "passive"))
      (node (ref "U2") (pin "23") (pinfunction "IO15_23") (pintype "bidirectional"))
    )
    (net (code "20") (name "MISO") (class "Default")
      (node (ref "D12") (pin "2") (pinfunction "2_2") (pintype "passive"))
      (node (ref "J4") (pin "P7") (pinfunction "DAT0_P7") (pintype "bidirectional"))
      (node (ref "R8") (pin "1") (pinfunction "1_1") (pintype "passive"))
      (node (ref "TP6") (pin "TP") (pinfunction "TP_TP") (pintype "input"))
      (node (ref "U1") (pin "2") (pinfunction "DO(IO1)_2") (pintype "bidirectional"))
      (node (ref "U2") (pin "27") (pinfunction "IO2_27") (pintype "bidirectional"))
    )
    (net (code "21") (name "MOSI") (class "Default")
      (node (ref "D11") (pin "2") (pinfunction "2_2") (pintype "passive"))
      (node (ref "J1") (pin "14") (pinfunction "14_14") (pintype "bidirectional"))
      (node (ref "J4") (pin "P3") (pinfunction "CMD_P3") (pintype "bidirectional"))
      (node (ref "R7") (pin "1") (pinfunction "1_1") (pintype "passive"))
      (node (ref "TP7") (pin "TP") (pinfunction "TP_TP") (pintype "input"))
      (node (ref "U1") (pin "5") (pinfunction "DI(IO0)_5") (pintype "bidirectional"))
      (node (ref "U2") (pin "7") (pinfunction "IO7_7") (pintype "bidirectional"))
    )
    (net (code "22") (name "Net-(CHG_LED-PadC)") (class "Default")
      (node (ref "CHG_LED") (pin "C") (pinfunction "C_C") (pintype "passive"))
      (node (ref "R1_BAT") (pin "1") (pinfunction "1_1") (pintype "passive"))
    )
    (net (code "23") (name "Net-(D2-CATHODE)") (class "Default")
      (node (ref "C1_BAT1") (pin "1") (pinfunction "1_1") (pintype "passive"))
      (node (ref "D2") (pin "1") (pinfunction "CATHODE_1") (pintype "bidirectional"))
      (node (ref "IC4") (pin "1") (pinfunction "VIN_1") (pintype "bidirectional"))
      (node (ref "IC4") (pin "3") (pinfunction "CE_3") (pintype "bidirectional"))
      (node (ref "Q1") (pin "2") (pinfunction "S_2") (pintype "bidirectional"))
    )
    (net (code "24") (name "Net-(D3-A)") (class "Default")
      (node (ref "C4") (pin "1") (pinfunction "1_1") (pintype "passive"))
      (node (ref "D3") (pin "2") (pinfunction "A_2") (pintype "bidirectional"))
      (node (ref "D4") (pin "1") (pinfunction "K_1") (pintype "bidirectional"))
    )
    (net (code "25") (name "Net-(D7-CATHODE)") (class "Default")
      (node (ref "D7") (pin "1") (pinfunction "CATHODE_1") (pintype "bidirectional"))
      (node (ref "R_CAPACITOR") (pin "1") (pinfunction "1_1") (pintype "passive"))
    )
    (net (code "26") (name "Net-(EPD_C1-Pad2)") (class "Default")
      (node (ref "EPD_C1") (pin "2") (pinfunction "2_2") (pintype "passive"))
      (node (ref "J1") (pin "4") (pinfunction "4_4") (pintype "bidirectional"))
    )
    (net (code "27") (name "Net-(EPD_C2-Pad2)") (class "Default")
      (node (ref "EPD_C2") (pin "2") (pinfunction "2_2") (pintype "passive"))
      (node (ref "J1") (pin "5") (pinfunction "5_5") (pintype "bidirectional"))
    )
    (net (code "28") (name "Net-(EPD_C6-Pad2)") (class "Default")
      (node (ref "EPD_C6") (pin "2") (pinfunction "2_2") (pintype "passive"))
      (node (ref "J1") (pin "18") (pinfunction "18_18") (pintype "bidirectional"))
    )
    (net (code "29") (name "Net-(EPD_C7-Pad2)") (class "Default")
      (node (ref "EPD_C7") (pin "2") (pinfunction "2_2") (pintype "passive"))
      (node (ref "J1") (pin "19") (pinfunction "19_19") (pintype "bidirectional"))
    )
    (net (code "30") (name "Net-(EPD_C8-Pad2)") (class "Default")
      (node (ref "EPD_C8") (pin "2") (pinfunction "2_2") (pintype "passive"))
      (node (ref "J1") (pin "20") (pinfunction "20_20") (pintype "bidirectional"))
    )
    (net (code "31") (name "Net-(EPD_C10-Pad2)") (class "Default")
      (node (ref "EPD_C10") (pin "2") (pinfunction "2_2") (pintype "passive"))
      (node (ref "J1") (pin "22") (pinfunction "22_22") (pintype "bidirectional"))
    )
    (net (code "32") (name "Net-(EPD_C12-Pad2)") (class "Default")
      (node (ref "EPD_C12") (pin "2") (pinfunction "2_2") (pintype "passive"))
      (node (ref "J1") (pin "24") (pinfunction "24_24") (pintype "bidirectional"))
    )
    (net (code "33") (name "Net-(IC1-CT)") (class "Default")
      (node (ref "C_DELAY") (pin "1") (pinfunction "1_1") (pintype "passive"))
      (node (ref "IC1") (pin "5") (pinfunction "CT_5") (pintype "bidirectional"))
    )
    (net (code "34") (name "Net-(J2-PadA5)") (class "Default")
      (node (ref "J2") (pin "A5") (pinfunction "A5_A5") (pintype "bidirectional"))
      (node (ref "R2-USB1") (pin "2") (pinfunction "2_2") (pintype "passive"))
    )
    (net (code "35") (name "Net-(J2-PadB5)") (class "Default")
      (node (ref "J2") (pin "B5") (pinfunction "B5_B5") (pintype "bidirectional"))
      (node (ref "R2-USB") (pin "1") (pinfunction "1_1") (pintype "passive"))
    )
    (net (code "36") (name "Net-(MCP73831-PROG)") (class "Default")
      (node (ref "MCP73831") (pin "5") (pinfunction "PROG_5") (pintype "input"))
      (node (ref "R2_BAT") (pin "2") (pinfunction "2_2") (pintype "passive"))
    )
    (net (code "37") (name "Net-(MCP73831-STAT)") (class "Default")
      (node (ref "MCP73831") (pin "1") (pinfunction "STAT_1") (pintype "output"))
      (node (ref "R1_BAT") (pin "2") (pinfunction "2_2") (pintype "passive"))
    )
    (net (code "38") (name "PREVGH") (class "Default")
      (node (ref "D5") (pin "1") (pinfunction "K_1") (pintype "bidirectional"))
      (node (ref "EPD_C9") (pin "2") (pinfunction "2_2") (pintype "passive"))
      (node (ref "J1") (pin "21") (pinfunction "21_21") (pintype "bidirectional"))
    )
    (net (code "39") (name "PREVGL") (class "Default")
      (node (ref "D4") (pin "2") (pinfunction "A_2") (pintype "bidirectional"))
      (node (ref "EPD_C11") (pin "2") (pinfunction "2_2") (pintype "passive"))
      (node (ref "J1") (pin "23") (pinfunction "23_23") (pintype "bidirectional"))
    )
    (net (code "40") (name "RESE") (class "Default")
      (node (ref "J1") (pin "3") (pinfunction "3_3") (pintype "bidirectional"))
      (node (ref "Q3") (pin "2") (pinfunction "S_2") (pintype "bidirectional"))
      (node (ref "R3") (pin "2") (pinfunction "2_2") (pintype "passive"))
    )
    (net (code "41") (name "RESE'") (class "Default")
      (node (ref "R2") (pin "2") (pinfunction "2_2") (pintype "passive"))
      (node (ref "R3") (pin "1") (pinfunction "1_1") (pintype "passive"))
      (node (ref "SJ1") (pin "2") (pinfunction "2_2") (pintype "passive"))
    )
    (net (code "42") (name "RESET") (class "Default")
      (node (ref "C5") (pin "1") (pinfunction "1_1") (pintype "passive"))
      (node (ref "IC1") (pin "1") (pinfunction "VOUT_1") (pintype "bidirectional"))
      (node (ref "RESET_BUTTON") (pin "3") (pinfunction "3_3") (pintype "passive"))
      (node (ref "RESET_BUTTON") (pin "4") (pinfunction "4_4") (pintype "passive"))
      (node (ref "R_RESET") (pin "1") (pinfunction "1_1") (pintype "passive"))
      (node (ref "U2") (pin "3") (pinfunction "EN_3") (pintype "input"))
    )
    (net (code "43") (name "RTC_RST") (class "Default")
      (node (ref "U2") (pin "16") (pinfunction "IO18_16") (pintype "bidirectional"))
      (node (ref "U3") (pin "4") (pinfunction "~{RST}_4") (pintype "input"))
    )
    (net (code "44") (name "RX") (class "Default")
      (node (ref "TP2") (pin "TP") (pinfunction "TP_TP") (pintype "input"))
      (node (ref "U2") (pin "24") (pinfunction "RXD0/GPIO17_24") (pintype "bidirectional"))
    )
    (net (code "45") (name "SCK") (class "Default")
      (node (ref "D10") (pin "2") (pinfunction "2_2") (pintype "passive"))
      (node (ref "J1") (pin "13") (pinfunction "13_13") (pintype "bidirectional"))
      (node (ref "J4") (pin "P5") (pinfunction "CLK_P5") (pintype "bidirectional"))
      (node (ref "R6") (pin "1") (pinfunction "1_1") (pintype "passive"))
      (node (ref "TP8") (pin "TP") (pinfunction "TP_TP") (pintype "input"))
      (node (ref "U1") (pin "6") (pinfunction "CLK_6") (pintype "input"))
      (node (ref "U2") (pin "6") (pinfunction "IO6_6") (pintype "bidirectional"))
    )
    (net (code "46") (name "SCL") (class "Default")
      (node (ref "J3") (pin "4") (pinfunction "4_4") (pintype "passive"))
      (node (ref "R2-PINH") (pin "1") (pinfunction "1_1") (pintype "passive"))
      (node (ref "SENSOR2") (pin "4") (pinfunction "SCK_4") (pintype "input"))
      (node (ref "U2") (pin "20") (pinfunction "IO22_20") (pintype "bidirectional"))
      (node (ref "U3") (pin "16") (pinfunction "SCL_16") (pintype "input"))
      (node (ref "U4") (pin "7") (pinfunction "SCL_7") (pintype "input"))
    )
    (net (code "47") (name "SDA") (class "Default")
      (node (ref "J3") (pin "3") (pinfunction "3_3") (pintype "passive"))
      (node (ref "R1_PINH") (pin "1") (pinfunction "1_1") (pintype "passive"))
      (node (ref "SENSOR2") (pin "3") (pinfunction "SDI_3") (pintype "bidirectional"))
      (node (ref "U2") (pin "19") (pinfunction "IO21_19") (pintype "bidirectional"))
      (node (ref "U3") (pin "15") (pinfunction "SDA_15") (pintype "bidirectional"))
      (node (ref "U4") (pin "8") (pinfunction "SDA_8") (pintype "bidirectional"))
    )
    (net (code "48") (name "SRC") (class "Default")
      (node (ref "C4") (pin "2") (pinfunction "2_2") (pintype "passive"))
      (node (ref "D5") (pin "2") (pinfunction "A_2") (pintype "bidirectional"))
      (node (ref "L1") (pin "1") (pinfunction "1_1") (pintype "passive"))
      (node (ref "Q3") (pin "3") (pinfunction "D_3") (pintype "bidirectional"))
    )
    (net (code "49") (name "SS_SD") (class "Default")
      (node (ref "D8") (pin "2") (pinfunction "2_2") (pintype "passive"))
      (node (ref "J4") (pin "P2") (pinfunction "CD/DAT3_P2") (pintype "bidirectional"))
      (node (ref "R10") (pin "1") (pinfunction "1_1") (pintype "passive"))
      (node (ref "U2") (pin "4") (pinfunction "IO4_4") (pintype "bidirectional"))
    )
    (net (code "50") (name "TX") (class "Default")
      (node (ref "TP1") (pin "TP") (pinfunction "TP_TP") (pintype "input"))
      (node (ref "U2") (pin "25") (pinfunction "TXD0/GPIO16_25") (pintype "bidirectional"))
    )
    (net (code "51") (name "USB_D+") (class "Default")
      (node (ref "D1") (pin "1") (pinfunction "I/O1_1_1") (pintype "bidirectional"))
      (node (ref "U2") (pin "14") (pinfunction "IO13_14") (pintype "bidirectional"))
    )
    (net (code "52") (name "USB_D-") (class "Default")
      (node (ref "D1") (pin "3") (pinfunction "I/O2_1_3") (pintype "bidirectional"))
      (node (ref "U2") (pin "13") (pinfunction "IO12_13") (pintype "bidirectional"))
    )
    (net (code "53") (name "VBAT") (class "Default")
      (node (ref "C2_BAT") (pin "1") (pinfunction "1_1") (pintype "passive"))
      (node (ref "MCP73831") (pin "3") (pinfunction "VBAT_3") (pintype "power_in"))
      (node (ref "Q1") (pin "3") (pinfunction "D_3") (pintype "bidirectional"))
      (node (ref "TP3") (pin "TP") (pinfunction "TP_TP") (pintype "input"))
      (node (ref "U4") (pin "2") (pinfunction "CELL_2") (pintype "power_in"))
      (node (ref "U4") (pin "3") (pinfunction "VDD_3") (pintype "power_in"))
    )
    (net (code "54") (name "VBUS") (class "Default")
      (node (ref "C1_BAT") (pin "1") (pinfunction "1_1") (pintype "passive"))
      (node (ref "C4_USB") (pin "1") (pinfunction "1_1") (pintype "passive"))
      (node (ref "C5_USB") (pin "1") (pinfunction "1_1") (pintype "passive"))
      (node (ref "CHG_LED") (pin "A") (pinfunction "A_A") (pintype "passive"))
      (node (ref "D1") (pin "5") (pinfunction "VBUS_5") (pintype "bidirectional"))
      (node (ref "D2") (pin "2") (pinfunction "ANODE_2") (pintype "bidirectional"))
      (node (ref "MCP73831") (pin "4") (pinfunction "VIN_4") (pintype "power_in"))
      (node (ref "PFMF.050.1") (pin "2") (pinfunction "2_2") (pintype "passive"))
      (node (ref "Q1") (pin "1") (pinfunction "G_1") (pintype "bidirectional"))
      (node (ref "R1_PWRUSB") (pin "2") (pinfunction "2_2") (pintype "passive"))
      (node (ref "TP14") (pin "TP") (pinfunction "TP_TP") (pintype "input"))
    )
    (net (code "55") (name "VRTC") (class "Default")
      (node (ref "C11") (pin "1") (pinfunction "1_1") (pintype "passive"))
      (node (ref "C8") (pin "1") (pinfunction "1_1") (pintype "passive"))
      (node (ref "R_CAPACITOR") (pin "2") (pinfunction "2_2") (pintype "passive"))
      (node (ref "U3") (pin "14") (pinfunction "VBAT_14") (pintype "power_in"))
    )
    (net (code "56") (name "VUSB") (class "Default")
      (node (ref "J2") (pin "A4") (pinfunction "A4_A4") (pintype "bidirectional"))
      (node (ref "J2") (pin "A9") (pinfunction "A9_A9") (pintype "bidirectional"))
      (node (ref "J2") (pin "B4") (pinfunction "B4_B4") (pintype "bidirectional"))
      (node (ref "J2") (pin "B9") (pinfunction "B9_B9") (pintype "bidirectional"))
      (node (ref "PFMF.050.1") (pin "1") (pinfunction "1_1") (pintype "passive"))
    )
    (net (code "57") (name "unconnected-(IC1-NC-Pad4)") (class "Default")
      (node (ref "IC1") (pin "4") (pinfunction "NC_4") (pintype "no_connect"))
    )
    (net (code "58") (name "unconnected-(IC4-NC-Pad4)") (class "Default")
      (node (ref "IC4") (pin "4") (pinfunction "NC_4") (pintype "no_connect"))
    )
    (net (code "59") (name "unconnected-(J1-Pad1)") (class "Default")
      (node (ref "J1") (pin "1") (pinfunction "1_1") (pintype "bidirectional"))
    )
    (net (code "60") (name "unconnected-(J1-Pad6)") (class "Default")
      (node (ref "J1") (pin "6") (pinfunction "6_6") (pintype "bidirectional"))
    )
    (net (code "61") (name "unconnected-(J1-Pad7)") (class "Default")
      (node (ref "J1") (pin "7") (pinfunction "7_7") (pintype "bidirectional"))
    )
    (net (code "62") (name "unconnected-(J2-PadA8)") (class "Default")
      (node (ref "J2") (pin "A8") (pinfunction "A8_A8") (pintype "bidirectional"))
    )
    (net (code "63") (name "unconnected-(J2-PadB8)") (class "Default")
      (node (ref "J2") (pin "B8") (pinfunction "B8_B8") (pintype "bidirectional"))
    )
    (net (code "64") (name "unconnected-(J4-DAT1-PadP8)") (class "Default")
      (node (ref "J4") (pin "P8") (pinfunction "DAT1_P8") (pintype "bidirectional"))
    )
    (net (code "65") (name "unconnected-(J4-DAT2-PadP1)") (class "Default")
      (node (ref "J4") (pin "P1") (pinfunction "DAT2_P1") (pintype "bidirectional"))
    )
    (net (code "66") (name "unconnected-(J4-DETECTION_1-PadS1)") (class "Default")
      (node (ref "J4") (pin "S1") (pinfunction "DETECTION_1_S1") (pintype "bidirectional"))
    )
    (net (code "67") (name "unconnected-(J4-DETECTION_2-PadS2)") (class "Default")
      (node (ref "J4") (pin "S2") (pinfunction "DETECTION_2_S2") (pintype "bidirectional"))
    )
    (net (code "68") (name "unconnected-(U2-NC-Pad22)") (class "Default")
      (node (ref "U2") (pin "22") (pinfunction "NC_22") (pintype "no_connect"))
    )
    (net (code "69") (name "unconnected-(U4-~{ALERT}-Pad5)") (class "Default")
      (node (ref "U4") (pin "5") (pinfunction "~{ALERT}_5") (pintype "output"))
    )
  )
)
